# webench_design_1160921_77_ad14_sim.net
KiCad netlist of a schematic drawn in Altium Designer
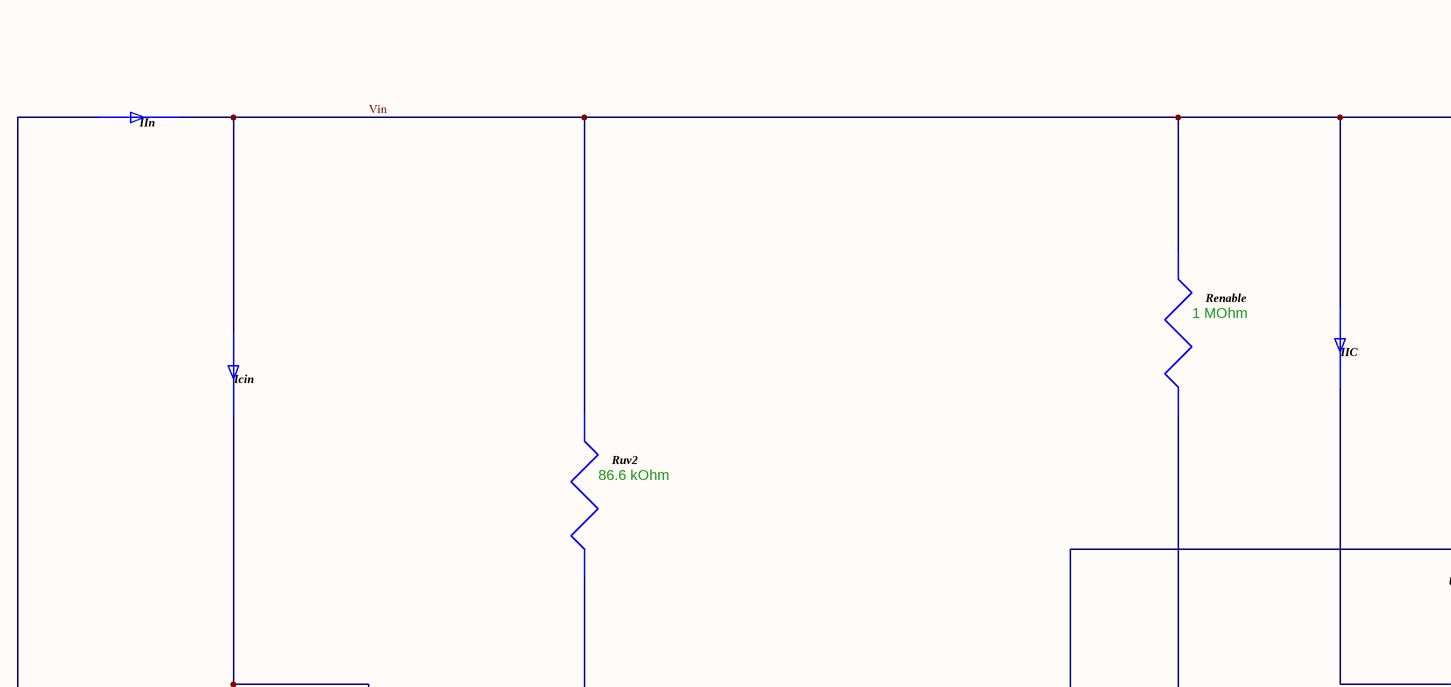
[diagram p0: webench_design_1160921_77_ad14_sim.SchDoc, top left]
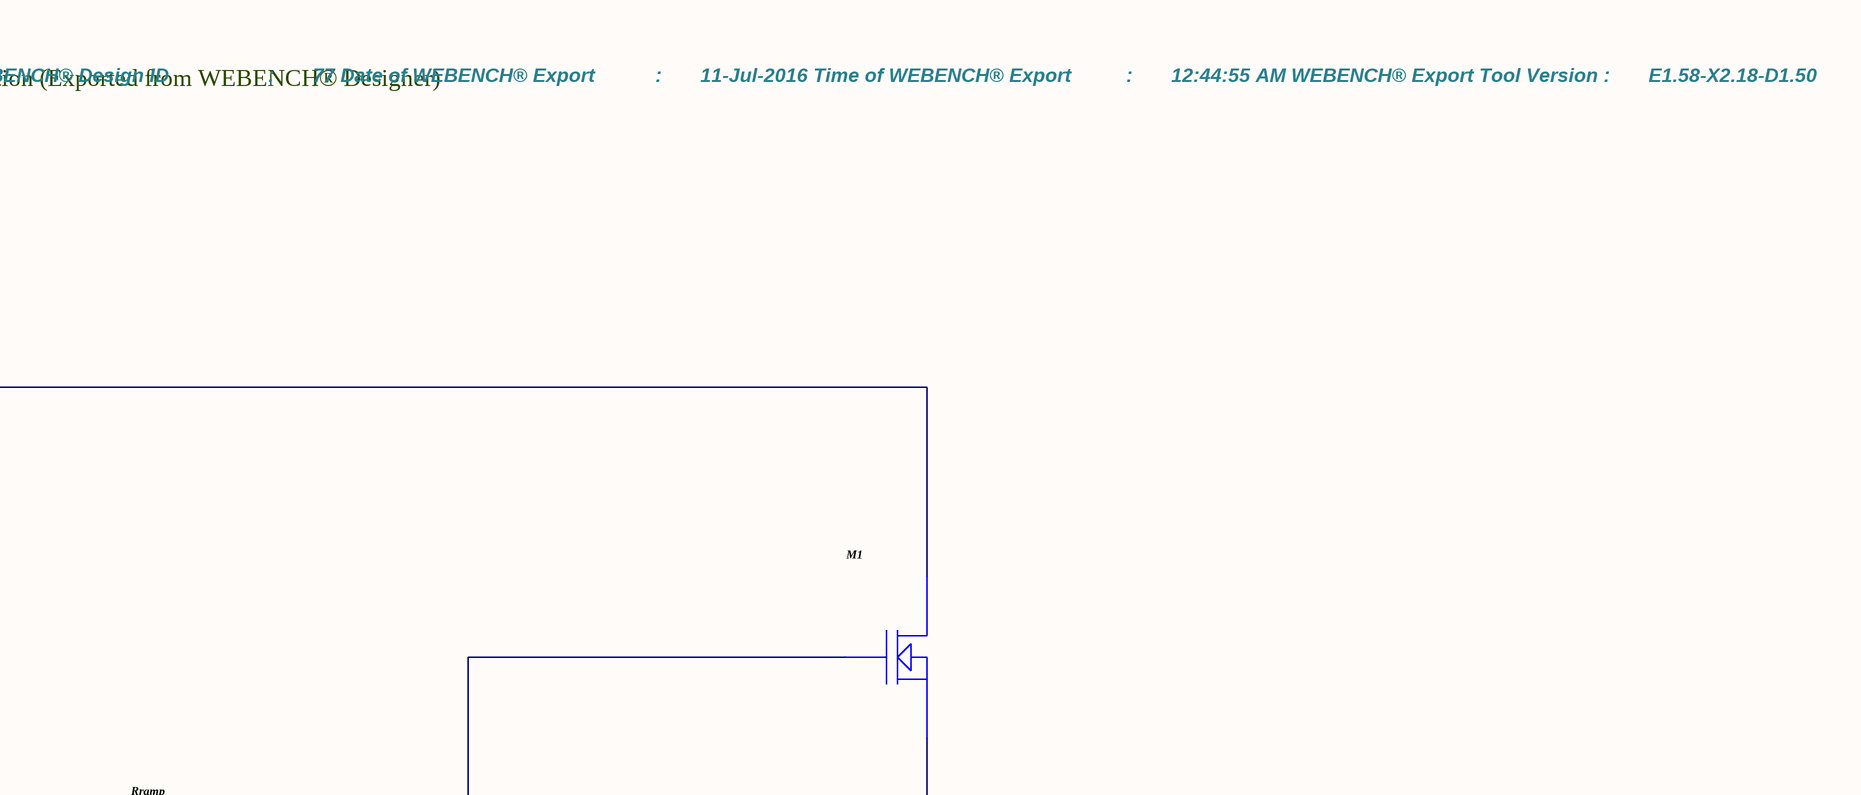
[diagram p1: webench_design_1160921_77_ad14_sim.SchDoc, top right]
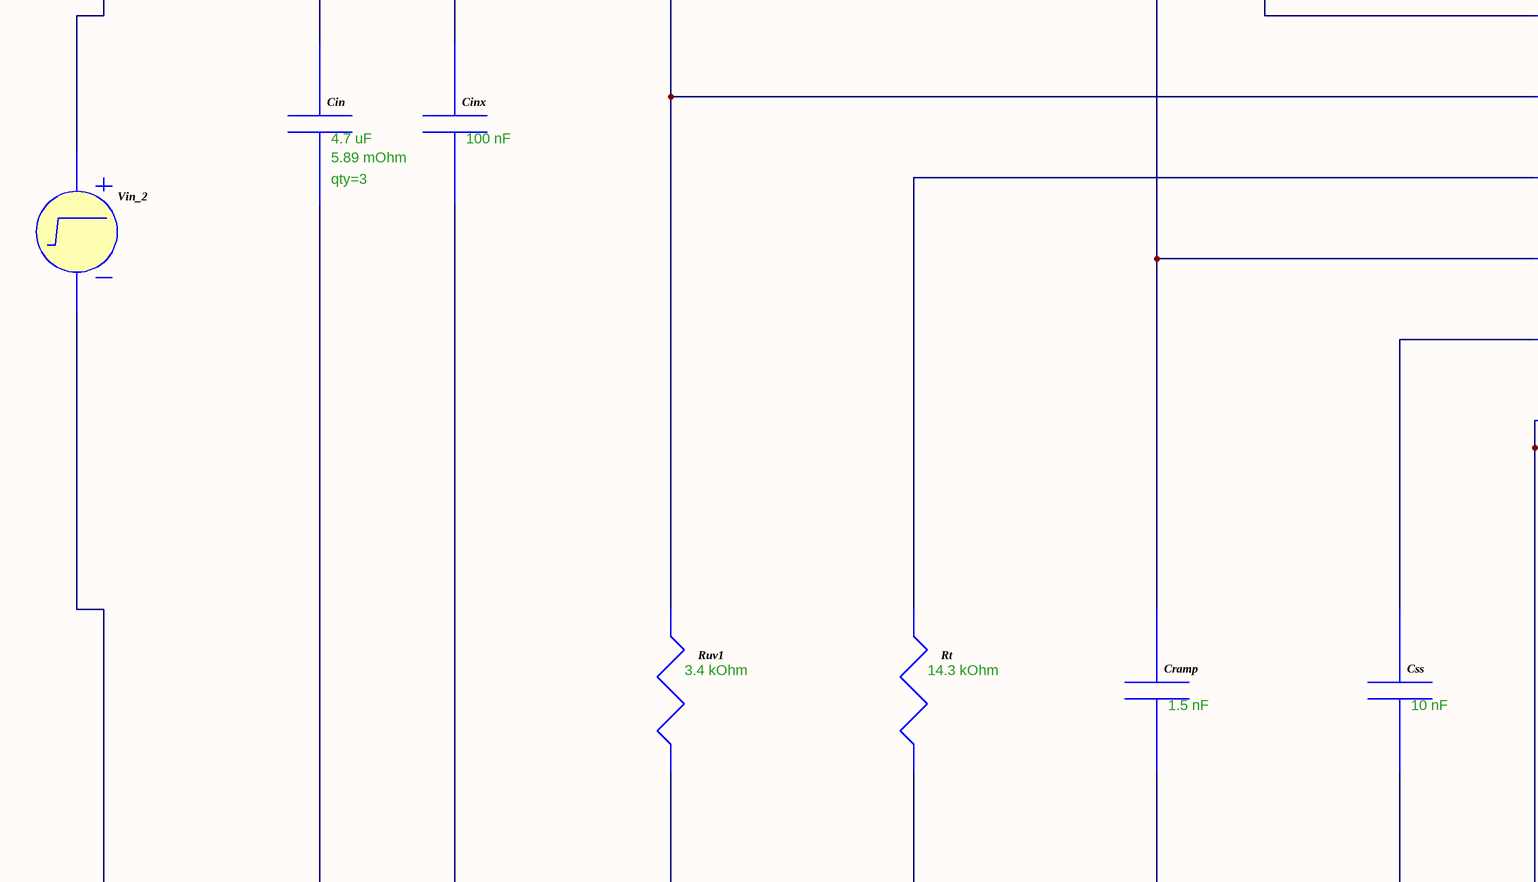
[diagram p2: webench_design_1160921_77_ad14_sim.SchDoc, bottom left]
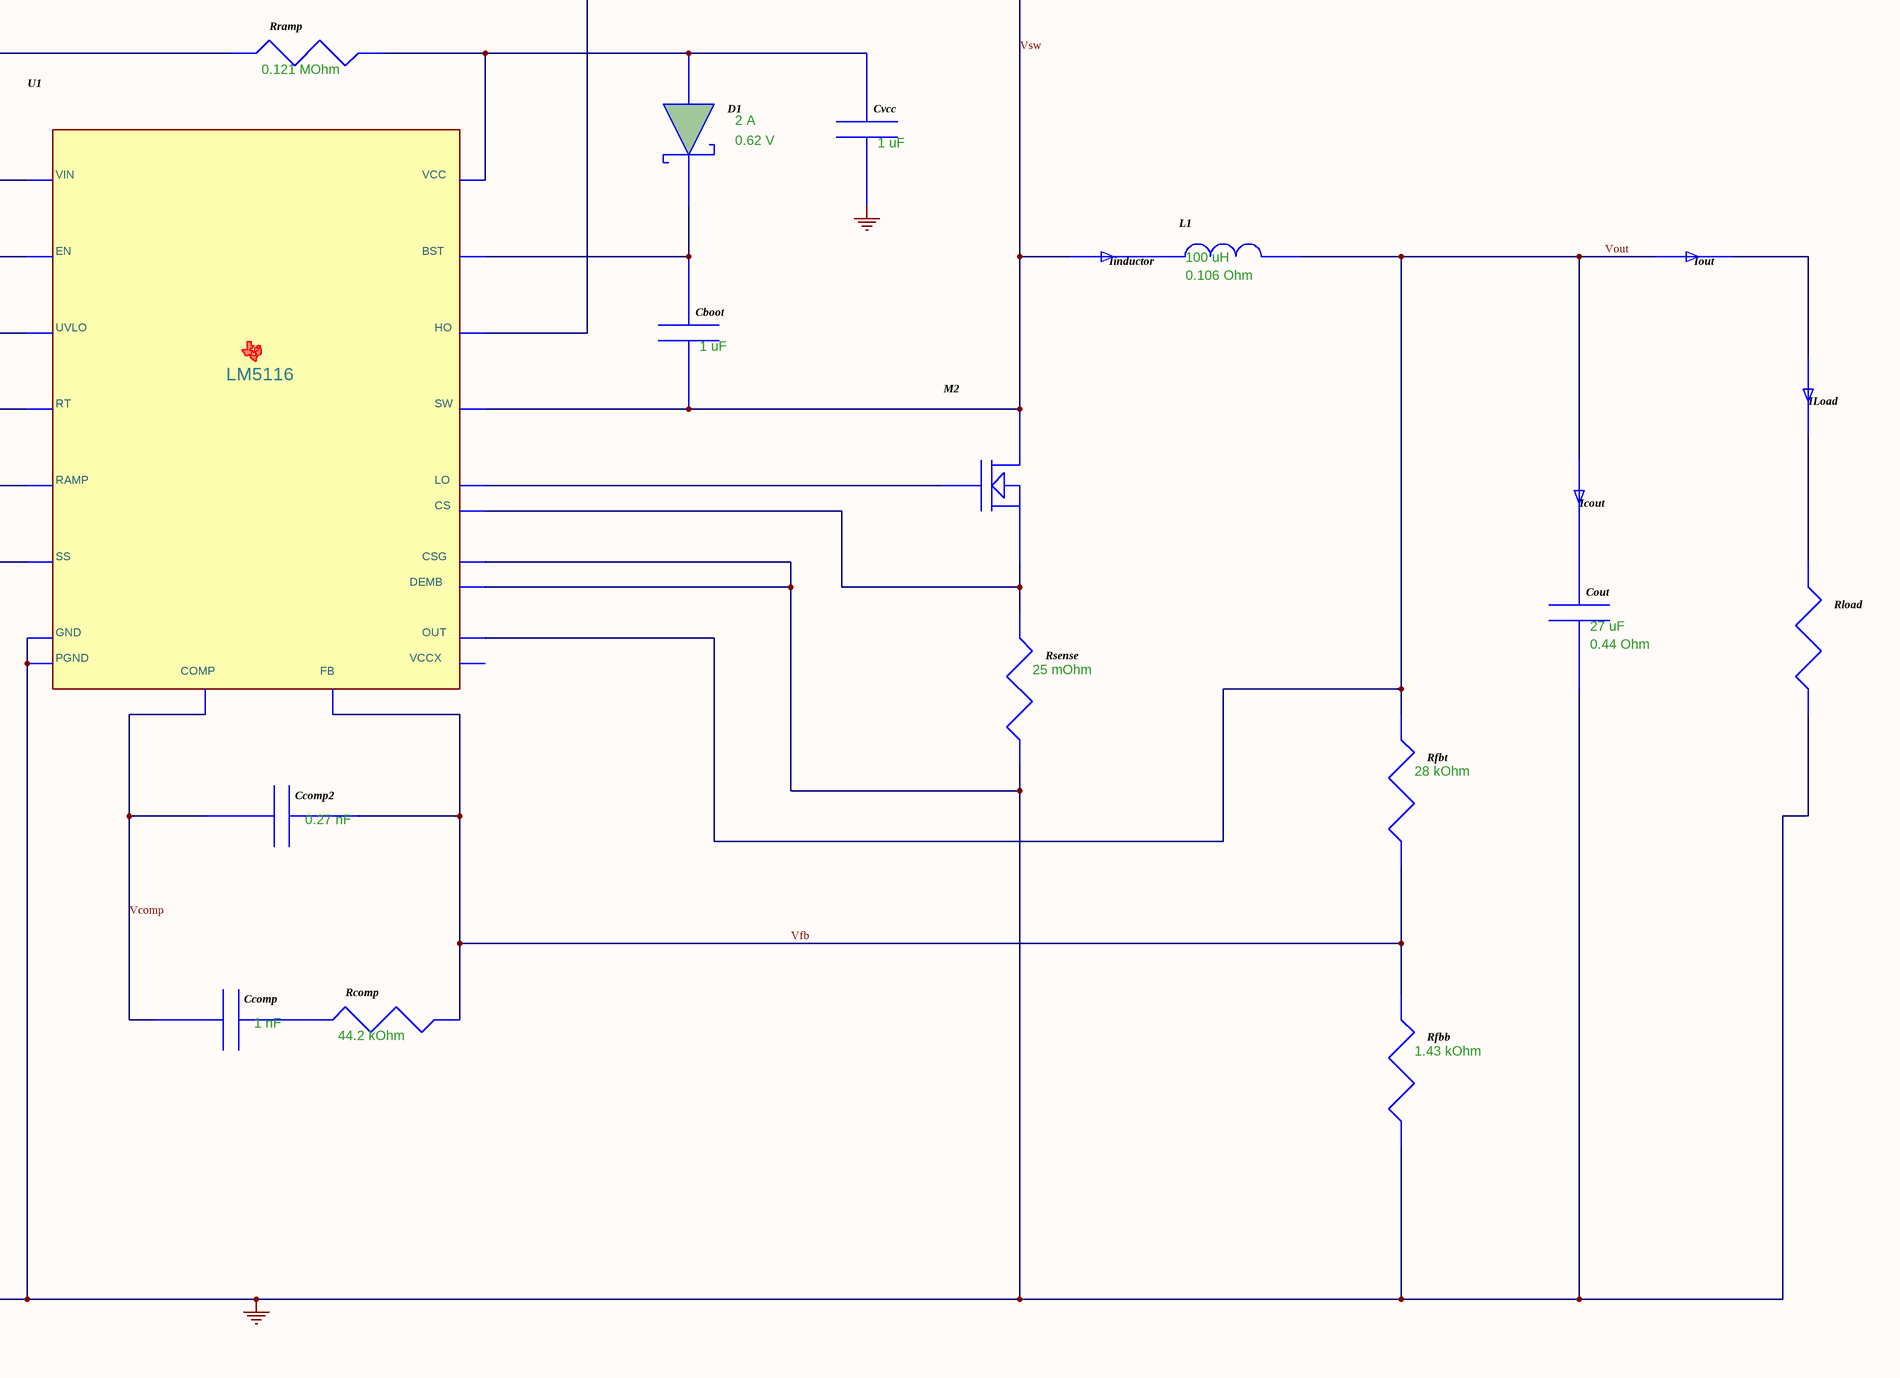
[diagram p3: webench_design_1160921_77_ad14_sim.SchDoc, bottom right]

(export (version "E")
  (design (tool "Eeschema 10.0.6"))
  (components
    (comp (ref "Cboot") (value "~") (libsource (lib "*") (part "Cboot")))
    (comp (ref "Ccomp") (value "~") (libsource (lib "*") (part "Ccomp")))
    (comp (ref "Ccomp2") (value "~") (libsource (lib "*") (part "Ccomp2")))
    (comp (ref "Cin") (value "~") (libsource (lib "*") (part "Cin")))
    (comp (ref "Cinx") (value "~") (libsource (lib "*") (part "Cinx")))
    (comp (ref "Cout") (value "~") (libsource (lib "*") (part "Cout")))
    (comp (ref "Cramp") (value "~") (libsource (lib "*") (part "Cramp")))
    (comp (ref "Css") (value "~") (libsource (lib "*") (part "Css")))
    (comp (ref "Cvcc") (value "~") (libsource (lib "*") (part "Cvcc")))
    (comp (ref "D1") (value "~") (libsource (lib "*") (part "D1")))
    (comp (ref "Icin")
      (value "~")
      (fields
        (field (name "PARAMETER0") "***********************************\n*     Created by WB Importer      *\n***********************************\n.SUBCKT Icin 1 2 \nV_Iprobe 1 2 0.0\n.ENDS")
      )
      (libsource (lib "*") (part "Icin"))
    )
    (comp (ref "Icout")
      (value "~")
      (fields
        (field (name "PARAMETER0") "***********************************\n*     Created by WB Importer      *\n***********************************\n.SUBCKT Icout 1 2 \nV_Iprobe 1 2 0.0\n.ENDS")
      )
      (libsource (lib "*") (part "Icout"))
    )
    (comp (ref "IIC")
      (value "~")
      (fields
        (field (name "PARAMETER0") "***********************************\n*     Created by WB Importer      *\n***********************************\n.SUBCKT IIC 1 2 \nV_Iprobe 1 2 0.0\n.ENDS")
      )
      (libsource (lib "*") (part "IIC"))
    )
    (comp (ref "IIn")
      (value "~")
      (fields
        (field (name "PARAMETER0") "***********************************\n*     Created by WB Importer      *\n***********************************\n.SUBCKT IIn 1 2 \nV_Iprobe 1 2 0.0\n.ENDS")
      )
      (libsource (lib "*") (part "IIn"))
    )
    (comp (ref "Iinductor")
      (value "~")
      (fields
        (field (name "PARAMETER0") "***********************************\n*     Created by WB Importer      *\n***********************************\n.SUBCKT Iinductor 1 2 \nV_Iprobe 1 2 0.0\n.ENDS")
      )
      (libsource (lib "*") (part "Iinductor"))
    )
    (comp (ref "ILoad")
      (value "~")
      (fields
        (field (name "PARAMETER0") "***********************************\n*     Created by WB Importer      *\n***********************************\n.SUBCKT ILoad 1 2 \nV_Iprobe 1 2 0.0\n.ENDS")
      )
      (libsource (lib "*") (part "ILoad"))
    )
    (comp (ref "Iout")
      (value "~")
      (fields
        (field (name "PARAMETER0") "***********************************\n*     Created by WB Importer      *\n***********************************\n.SUBCKT Iout 1 2 \nV_Iprobe 1 2 0.0\n.ENDS")
      )
      (libsource (lib "*") (part "Iout"))
    )
    (comp (ref "L1") (value "~") (libsource (lib "*") (part "L1")))
    (comp (ref "M1") (value "~") (libsource (lib "*") (part "M1")))
    (comp (ref "M2") (value "~") (libsource (lib "*") (part "M2")))
    (comp (ref "Rcomp") (value "~") (libsource (lib "*") (part "Rcomp")))
    (comp (ref "Renable") (value "~") (libsource (lib "*") (part "Renable")))
    (comp (ref "Rfbb") (value "~") (libsource (lib "*") (part "Rfbb")))
    (comp (ref "Rfbt") (value "~") (libsource (lib "*") (part "Rfbt")))
    (comp (ref "Rload") (value "~") (libsource (lib "*") (part "Rload")))
    (comp (ref "Rramp") (value "~") (libsource (lib "*") (part "Rramp")))
    (comp (ref "Rsense") (value "~") (libsource (lib "*") (part "Rsense")))
    (comp (ref "Rt") (value "~") (libsource (lib "*") (part "Rt")))
    (comp (ref "Ruv1") (value "~") (libsource (lib "*") (part "Ruv1")))
    (comp (ref "Ruv2") (value "~") (libsource (lib "*") (part "Ruv2")))
    (comp (ref "U1") (value "~") (libsource (lib "*") (part "U1")))
    (comp (ref "Vin_2") (value "~") (libsource (lib "*") (part "Vin_2")))
  )
  (nets
    (net (code "1") (name "/Vcomp") (class "Default")
      (node (ref "Ccomp") (pin "8") (pinfunction "8_8") (pintype "passive"))
      (node (ref "Ccomp2") (pin "8") (pinfunction "8_8") (pintype "passive"))
      (node (ref "U1") (pin "COMP") (pinfunction "COMP_COMP") (pintype "passive"))
    )
    (net (code "2") (name "/Vfb") (class "Default")
      (node (ref "Ccomp2") (pin "9") (pinfunction "9_9") (pintype "passive"))
      (node (ref "Rcomp") (pin "9") (pinfunction "9_9") (pintype "passive"))
      (node (ref "Rfbb") (pin "9") (pinfunction "9_9") (pintype "passive"))
      (node (ref "Rfbt") (pin "9") (pinfunction "9_9") (pintype "passive"))
      (node (ref "U1") (pin "FB") (pinfunction "FB_FB") (pintype "passive"))
    )
    (net (code "3") (name "/Vin") (class "Default")
      (node (ref "IIC") (pin "1") (pinfunction "1_1") (pintype "passive"))
      (node (ref "IIn") (pin "2") (pinfunction "2_2") (pintype "passive"))
      (node (ref "Icin") (pin "1") (pinfunction "1_1") (pintype "passive"))
      (node (ref "M1") (pin "drain") (pinfunction "drain_drain") (pintype "passive"))
      (node (ref "Renable") (pin "3") (pinfunction "3_3") (pintype "passive"))
      (node (ref "Ruv2") (pin "3") (pinfunction "3_3") (pintype "passive"))
    )
    (net (code "4") (name "/Vout") (class "Default")
      (node (ref "Icout") (pin "1") (pinfunction "1_1") (pintype "passive"))
      (node (ref "Iout") (pin "1") (pinfunction "1_1") (pintype "passive"))
      (node (ref "L1") (pin "2") (pinfunction "2_2") (pintype "passive"))
      (node (ref "Rfbt") (pin "13") (pinfunction "13_13") (pintype "passive"))
      (node (ref "U1") (pin "OUT") (pinfunction "OUT_OUT") (pintype "passive"))
    )
    (net (code "5") (name "/Vsw") (class "Default")
      (node (ref "Cboot") (pin "14") (pinfunction "14_14") (pintype "passive"))
      (node (ref "Iinductor") (pin "1") (pinfunction "1_1") (pintype "passive"))
      (node (ref "M1") (pin "source") (pinfunction "source_source") (pintype "passive"))
      (node (ref "M2") (pin "d1") (pinfunction "d1_d1") (pintype "passive"))
      (node (ref "U1") (pin "SW") (pinfunction "SW_SW") (pintype "passive"))
    )
    (net (code "6") (name "GND") (class "Default")
      (node (ref "Cin") (pin "2") (pinfunction "2_2") (pintype "passive"))
      (node (ref "Cinx") (pin "0") (pinfunction "0_0") (pintype "passive"))
      (node (ref "Cout") (pin "4") (pinfunction "4_4") (pintype "passive"))
      (node (ref "Cramp") (pin "0") (pinfunction "0_0") (pintype "passive"))
      (node (ref "Css") (pin "0") (pinfunction "0_0") (pintype "passive"))
      (node (ref "Cvcc") (pin "0") (pinfunction "0_0") (pintype "passive"))
      (node (ref "Rfbb") (pin "0") (pinfunction "0_0") (pintype "passive"))
      (node (ref "Rload") (pin "2") (pinfunction "2_2") (pintype "passive"))
      (node (ref "Rsense") (pin "0") (pinfunction "0_0") (pintype "passive"))
      (node (ref "Rt") (pin "0") (pinfunction "0_0") (pintype "passive"))
      (node (ref "Ruv1") (pin "0") (pinfunction "0_0") (pintype "passive"))
      (node (ref "U1") (pin "CSG") (pinfunction "CSG_CSG") (pintype "passive"))
      (node (ref "U1") (pin "DEMB") (pinfunction "DEMB_DEMB") (pintype "passive"))
      (node (ref "U1") (pin "GND") (pinfunction "GND_GND") (pintype "passive"))
      (node (ref "U1") (pin "PGND") (pinfunction "PGND_PGND") (pintype "passive"))
      (node (ref "Vin_2") (pin "2") (pinfunction "2_2") (pintype "passive"))
    )
    (net (code "7") (name "Net-(Cboot-Pad11)") (class "Default")
      (node (ref "Cboot") (pin "11") (pinfunction "11_11") (pintype "passive"))
      (node (ref "D1") (pin "11") (pinfunction "11_11") (pintype "passive"))
      (node (ref "U1") (pin "BST") (pinfunction "BST_BST") (pintype "passive"))
    )
    (net (code "8") (name "Net-(Ccomp-Pad24)") (class "Default")
      (node (ref "Ccomp") (pin "24") (pinfunction "24_24") (pintype "passive"))
      (node (ref "Rcomp") (pin "24") (pinfunction "24_24") (pintype "passive"))
    )
    (net (code "9") (name "Net-(Cin-Pad1)") (class "Default")
      (node (ref "Cin") (pin "1") (pinfunction "1_1") (pintype "passive"))
      (node (ref "Cinx") (pin "1") (pinfunction "1_1") (pintype "passive"))
      (node (ref "Icin") (pin "2") (pinfunction "2_2") (pintype "passive"))
    )
    (net (code "10") (name "Net-(Cout-Pad2)") (class "Default")
      (node (ref "Cout") (pin "2") (pinfunction "2_2") (pintype "passive"))
      (node (ref "Icout") (pin "2") (pinfunction "2_2") (pintype "passive"))
    )
    (net (code "11") (name "Net-(Cramp-Pad6)") (class "Default")
      (node (ref "Cramp") (pin "6") (pinfunction "6_6") (pintype "passive"))
      (node (ref "Rramp") (pin "6") (pinfunction "6_6") (pintype "passive"))
      (node (ref "U1") (pin "RAMP") (pinfunction "RAMP_RAMP") (pintype "passive"))
    )
    (net (code "12") (name "Net-(Css-Pad7)") (class "Default")
      (node (ref "Css") (pin "7") (pinfunction "7_7") (pintype "passive"))
      (node (ref "U1") (pin "SS") (pinfunction "SS_SS") (pintype "passive"))
    )
    (net (code "13") (name "Net-(Cvcc-Pad10)") (class "Default")
      (node (ref "Cvcc") (pin "10") (pinfunction "10_10") (pintype "passive"))
      (node (ref "D1") (pin "10") (pinfunction "10_10") (pintype "passive"))
      (node (ref "Rramp") (pin "10") (pinfunction "10_10") (pintype "passive"))
      (node (ref "U1") (pin "VCC") (pinfunction "VCC_VCC") (pintype "passive"))
    )
    (net (code "14") (name "Net-(IIC-Pad2)") (class "Default")
      (node (ref "IIC") (pin "2") (pinfunction "2_2") (pintype "passive"))
      (node (ref "U1") (pin "VIN") (pinfunction "VIN_VIN") (pintype "passive"))
    )
    (net (code "15") (name "Net-(IIn-Pad1)") (class "Default")
      (node (ref "IIn") (pin "1") (pinfunction "1_1") (pintype "passive"))
      (node (ref "Vin_2") (pin "1") (pinfunction "1_1") (pintype "passive"))
    )
    (net (code "16") (name "Net-(ILoad-Pad1)") (class "Default")
      (node (ref "ILoad") (pin "1") (pinfunction "1_1") (pintype "passive"))
      (node (ref "Iout") (pin "2") (pinfunction "2_2") (pintype "passive"))
    )
    (net (code "17") (name "Net-(ILoad-Pad2)") (class "Default")
      (node (ref "ILoad") (pin "2") (pinfunction "2_2") (pintype "passive"))
      (node (ref "Rload") (pin "1") (pinfunction "1_1") (pintype "passive"))
    )
    (net (code "18") (name "Net-(Iinductor-Pad2)") (class "Default")
      (node (ref "Iinductor") (pin "2") (pinfunction "2_2") (pintype "passive"))
      (node (ref "L1") (pin "1") (pinfunction "1_1") (pintype "passive"))
    )
    (net (code "19") (name "Net-(M1-Padgate)") (class "Default")
      (node (ref "M1") (pin "gate") (pinfunction "gate_gate") (pintype "passive"))
      (node (ref "U1") (pin "HO") (pinfunction "HO_HO") (pintype "passive"))
    )
    (net (code "20") (name "Net-(M2-Padg1)") (class "Default")
      (node (ref "M2") (pin "g1") (pinfunction "g1_g1") (pintype "passive"))
      (node (ref "U1") (pin "LO") (pinfunction "LO_LO") (pintype "passive"))
    )
    (net (code "21") (name "Net-(M2-Pads1)") (class "Default")
      (node (ref "M2") (pin "s1") (pinfunction "s1_s1") (pintype "passive"))
      (node (ref "Rsense") (pin "12") (pinfunction "12_12") (pintype "passive"))
      (node (ref "U1") (pin "CS") (pinfunction "CS_CS") (pintype "passive"))
    )
    (net (code "22") (name "Net-(Renable-Pad5)") (class "Default")
      (node (ref "Renable") (pin "5") (pinfunction "5_5") (pintype "passive"))
      (node (ref "U1") (pin "EN") (pinfunction "EN_EN") (pintype "passive"))
    )
    (net (code "23") (name "Net-(Rt-Pad4)") (class "Default")
      (node (ref "Rt") (pin "4") (pinfunction "4_4") (pintype "passive"))
      (node (ref "U1") (pin "RT") (pinfunction "RT_RT") (pintype "passive"))
    )
    (net (code "24") (name "Net-(Ruv1-Pad2)") (class "Default")
      (node (ref "Ruv1") (pin "2") (pinfunction "2_2") (pintype "passive"))
      (node (ref "Ruv2") (pin "2") (pinfunction "2_2") (pintype "passive"))
      (node (ref "U1") (pin "UVLO") (pinfunction "UVLO_UVLO") (pintype "passive"))
    )
    (net (code "25") (name "unconnected-(U1-PadVCCX)") (class "Default")
      (node (ref "U1") (pin "VCCX") (pinfunction "VCCX_VCCX") (pintype "passive"))
    )
  )
)
